# 2_ADSTM32-MCU.net
KiCad netlist of a schematic drawn in Altium Designer
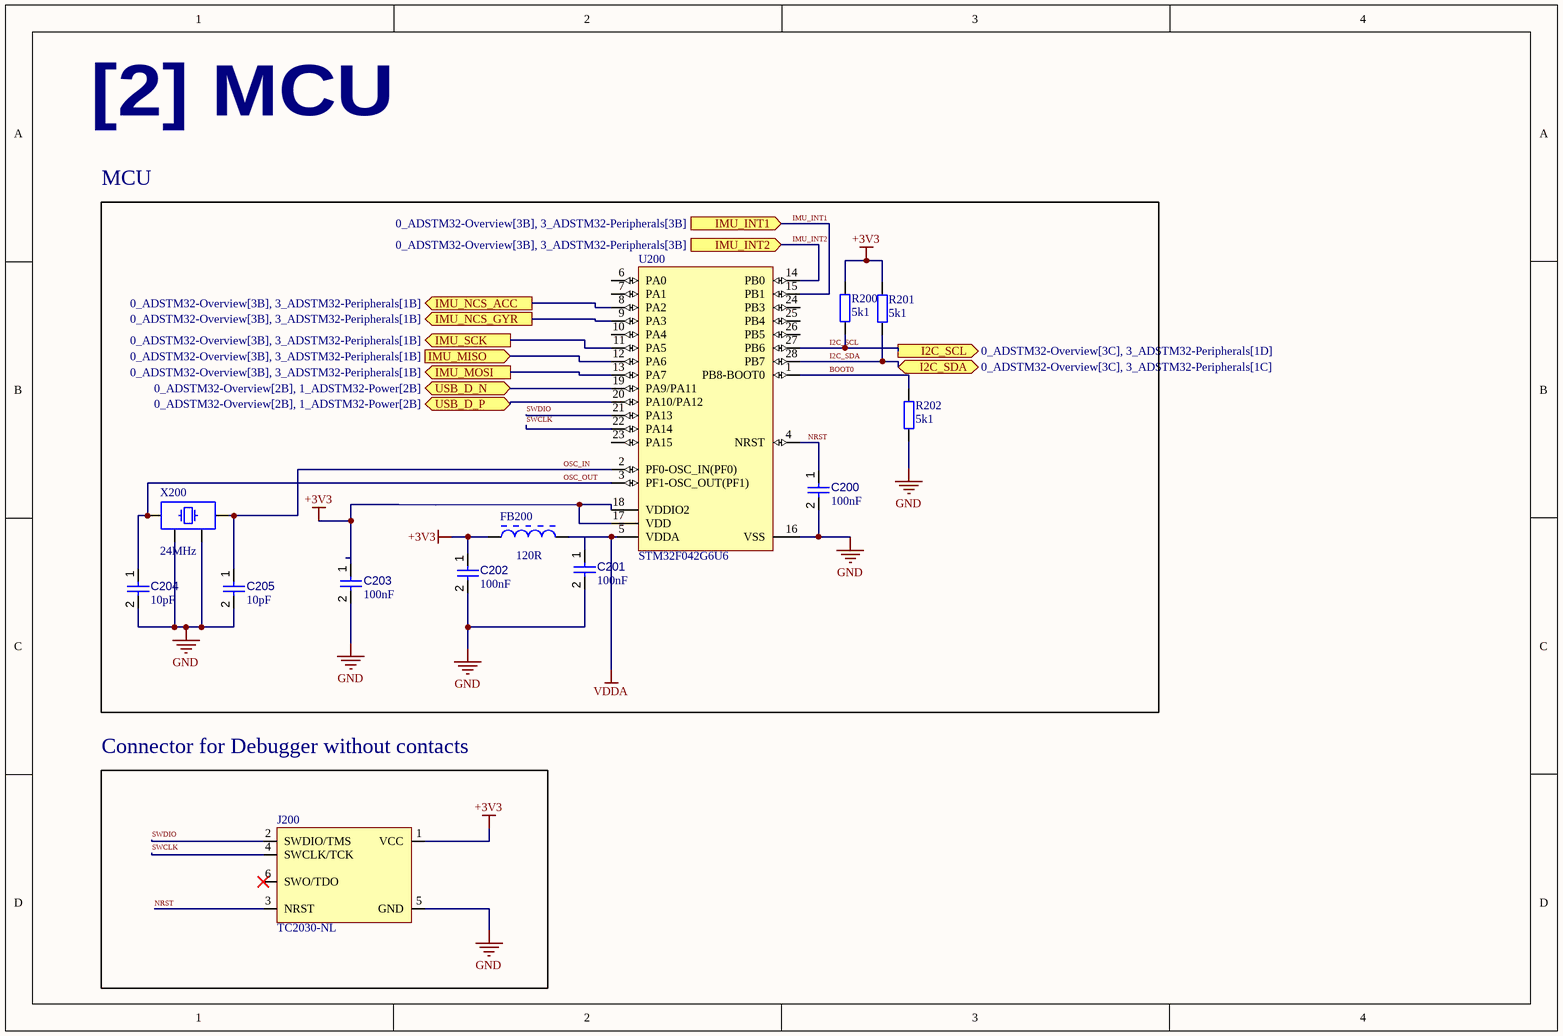
[diagram p0: 2_ADSTM32-MCU.SchDoc]

(export (version "E")
  (design (tool "Eeschema 10.0.6"))
  (components
    (comp (ref "C200")
      (value "100nF")
      (footprint "CAPC1608X90X40NL10T20")
      (description "Chip Capacitor, 100 nF, +/- 10%, 50 V, 0603 (1608 Metric)")
      (fields (field (name "TOLERANCE") "10%") (field (name "Comment") "Capacitor 100 nF +/-10% 50 V 0603"))
      (libsource (lib "Technische Universität Darmstadt -  Institut für Stromrichtertechnik und Antriebsregelung") (part "CAP-NP-2"))
    )
    (comp (ref "C201")
      (value "100nF")
      (footprint "CAPC1608X90X40NL10T20")
      (description "Chip Capacitor, 100 nF, +/- 10%, 50 V, 0603 (1608 Metric)")
      (fields (field (name "TOLERANCE") "10%") (field (name "Comment") "Capacitor 100 nF +/-10% 50 V 0603"))
      (libsource (lib "Technische Universität Darmstadt -  Institut für Stromrichtertechnik und Antriebsregelung") (part "CAP-NP-2"))
    )
    (comp (ref "C202")
      (value "100nF")
      (footprint "CAPC1608X90X40NL10T20")
      (description "Chip Capacitor, 100 nF, +/- 10%, 50 V, 0603 (1608 Metric)")
      (fields (field (name "TOLERANCE") "10%") (field (name "Comment") "Capacitor 100 nF +/-10% 50 V 0603"))
      (libsource (lib "Technische Universität Darmstadt -  Institut für Stromrichtertechnik und Antriebsregelung") (part "CAP-NP-2"))
    )
    (comp (ref "C203")
      (value "100nF")
      (footprint "CAPC1608X90X40NL10T20")
      (description "Chip Capacitor, 100 nF, +/- 10%, 50 V, 0603 (1608 Metric)")
      (fields (field (name "TOLERANCE") "10%") (field (name "Comment") "Capacitor 100 nF +/-10% 50 V 0603"))
      (libsource (lib "Technische Universität Darmstadt -  Institut für Stromrichtertechnik und Antriebsregelung") (part "CAP-NP-2"))
    )
    (comp (ref "C204")
      (value "10pF")
      (footprint "CAPC1608X90X40NL10T20")
      (description "Chip Capacitor, 100 nF, +/- 10%, 50 V, 0603 (1608 Metric)")
      (fields (field (name "TOLERANCE") "10%") (field (name "Comment") "Capacitor 100 nF +/-10% 50 V 0603"))
      (libsource (lib "Technische Universität Darmstadt -  Institut für Stromrichtertechnik und Antriebsregelung") (part "CAP-NP-2"))
    )
    (comp (ref "C205")
      (value "10pF")
      (footprint "CAPC1608X90X40NL10T20")
      (description "Chip Capacitor, 100 nF, +/- 10%, 50 V, 0603 (1608 Metric)")
      (fields (field (name "TOLERANCE") "10%") (field (name "Comment") "Capacitor 100 nF +/-10% 50 V 0603"))
      (libsource (lib "Technische Universität Darmstadt -  Institut für Stromrichtertechnik und Antriebsregelung") (part "CAP-NP-2"))
    )
    (comp (ref "FB200")
      (value "120R")
      (footprint "INDC2013X105X50ML20T20")
      (description "Chip Ferrite Bead, 120 Ohm,")
      (fields (field (name "TOLERANCE") "25%") (field (name "MANUFACTURER") "Murata"))
      (libsource (lib "Technische Universität Darmstadt -  Institut für Stromrichtertechnik und Antriebsregelung") (part "IND-FB-2"))
    )
    (comp (ref "J200")
      (value "TC2030-NL")
      (footprint "TC2030-NL-FP")
      (description "Tag-Connect No-Solder SWD Debug Connector (No Legs) DO NOT PLACE")
      (fields
        (field (name "MANUFACTURER") "Tag-Connect")
        (field (name "MANUFACTURER PART NUMBER") "TC2030-NL-FP")
      )
      (libsource (lib "Schematic-Lib-PhilsLab") (part "TC2030-NL"))
    )
    (comp (ref "R200")
      (value "5k1")
      (footprint "RES_0603")
      (description "Resistor SMD 0603")
      (libsource (lib "Schematic-Lib-PhilsLab") (part "RES_0603"))
    )
    (comp (ref "R201")
      (value "5k1")
      (footprint "RES_0603")
      (description "Resistor SMD 0603")
      (libsource (lib "Schematic-Lib-PhilsLab") (part "RES_0603"))
    )
    (comp (ref "R202")
      (value "5k1")
      (footprint "RES_0603")
      (description "Resistor SMD 0603")
      (libsource (lib "Schematic-Lib-PhilsLab") (part "RES_0603"))
    )
    (comp (ref "U200")
      (value "STM32F042G6U6")
      (footprint "STM-UFQFPN28_V")
      (fields (field (name "MANUFACTURER") "STMicroelectronics"))
      (libsource (lib "Altium Content Vault") (part "MC-ARM-STM32F042-UFQFPN28"))
    )
    (comp (ref "X200")
      (value "24MHz")
      (footprint "XTAL_3225")
      (description "Crystal SMD 24MHz 10PPM 7pF 3225")
      (fields
        (field (name "MANUFACTURER") "Epson")
        (field (name "MANUFACTURER PART NUMBER") "TSX-3225 24.0000MF15X-AC")
      )
      (libsource (lib "Schematic-Lib-PhilsLab") (part "TSX-3225_24.0000MF15X-AC"))
    )
  )
  (nets
    (net (code "1") (name "+3V3") (class "Default")
      (node (ref "C202") (pin "1") (pinfunction "1_1") (pintype "passive"))
      (node (ref "C203") (pin "1") (pinfunction "1_1") (pintype "passive"))
      (node (ref "FB200") (pin "1") (pinfunction "1_1") (pintype "passive"))
      (node (ref "J200") (pin "1") (pinfunction "VCC_1") (pintype "passive"))
      (node (ref "R200") (pin "2") (pinfunction "2_2") (pintype "passive"))
      (node (ref "R201") (pin "2") (pinfunction "2_2") (pintype "passive"))
      (node (ref "U200") (pin "17") (pinfunction "VDD_17") (pintype "power_in"))
      (node (ref "U200") (pin "18") (pinfunction "VDDIO2_18") (pintype "power_in"))
    )
    (net (code "2") (name "/BOOT0") (class "Default")
      (node (ref "R202") (pin "2") (pinfunction "2_2") (pintype "passive"))
      (node (ref "U200") (pin "1") (pinfunction "PB8-BOOT0_1") (pintype "bidirectional"))
    )
    (net (code "3") (name "/I2C_SCL") (class "Default")
      (node (ref "R200") (pin "1") (pinfunction "1_1") (pintype "passive"))
      (node (ref "U200") (pin "27") (pinfunction "PB6_27") (pintype "bidirectional"))
    )
    (net (code "4") (name "/I2C_SDA") (class "Default")
      (node (ref "R201") (pin "1") (pinfunction "1_1") (pintype "passive"))
      (node (ref "U200") (pin "28") (pinfunction "PB7_28") (pintype "bidirectional"))
    )
    (net (code "5") (name "/IMU_INT1") (class "Default")
      (node (ref "U200") (pin "15") (pinfunction "PB1_15") (pintype "bidirectional"))
    )
    (net (code "6") (name "/IMU_INT2") (class "Default")
      (node (ref "U200") (pin "14") (pinfunction "PB0_14") (pintype "bidirectional"))
    )
    (net (code "7") (name "/IMU_MISO") (class "Default")
      (node (ref "U200") (pin "12") (pinfunction "PA6_12") (pintype "bidirectional"))
    )
    (net (code "8") (name "/IMU_MOSI") (class "Default")
      (node (ref "U200") (pin "13") (pinfunction "PA7_13") (pintype "bidirectional"))
    )
    (net (code "9") (name "/IMU_NCS_ACC") (class "Default")
      (node (ref "U200") (pin "8") (pinfunction "PA2_8") (pintype "bidirectional"))
    )
    (net (code "10") (name "/IMU_NCS_GYR") (class "Default")
      (node (ref "U200") (pin "9") (pinfunction "PA3_9") (pintype "bidirectional"))
    )
    (net (code "11") (name "/IMU_SCK") (class "Default")
      (node (ref "U200") (pin "11") (pinfunction "PA5_11") (pintype "bidirectional"))
    )
    (net (code "12") (name "/NRST") (class "Default")
      (node (ref "C200") (pin "1") (pinfunction "1_1") (pintype "passive"))
      (node (ref "J200") (pin "3") (pinfunction "NRST_3") (pintype "passive"))
      (node (ref "U200") (pin "4") (pinfunction "NRST_4") (pintype "bidirectional"))
    )
    (net (code "13") (name "/OSC_IN") (class "Default")
      (node (ref "C205") (pin "1") (pinfunction "1_1") (pintype "passive"))
      (node (ref "U200") (pin "2") (pinfunction "PF0-OSC_IN(PF0)_2") (pintype "bidirectional"))
      (node (ref "X200") (pin "3") (pinfunction "3_3") (pintype "passive"))
    )
    (net (code "14") (name "/OSC_OUT") (class "Default")
      (node (ref "C204") (pin "1") (pinfunction "1_1") (pintype "passive"))
      (node (ref "U200") (pin "3") (pinfunction "PF1-OSC_OUT(PF1)_3") (pintype "bidirectional"))
      (node (ref "X200") (pin "1") (pinfunction "1_1") (pintype "passive"))
    )
    (net (code "15") (name "/SWCLK") (class "Default")
      (node (ref "J200") (pin "4") (pinfunction "SWCLK/TCK_4") (pintype "passive"))
      (node (ref "U200") (pin "22") (pinfunction "PA14_22") (pintype "bidirectional"))
    )
    (net (code "16") (name "/SWDIO") (class "Default")
      (node (ref "J200") (pin "2") (pinfunction "SWDIO/TMS_2") (pintype "passive"))
      (node (ref "U200") (pin "21") (pinfunction "PA13_21") (pintype "bidirectional"))
    )
    (net (code "17") (name "/USB_D_N") (class "Default")
      (node (ref "U200") (pin "19") (pinfunction "PA9/PA11_19") (pintype "bidirectional"))
    )
    (net (code "18") (name "/USB_D_P") (class "Default")
      (node (ref "U200") (pin "20") (pinfunction "PA10/PA12_20") (pintype "bidirectional"))
    )
    (net (code "19") (name "GND") (class "Default")
      (node (ref "C200") (pin "2") (pinfunction "2_2") (pintype "passive"))
      (node (ref "C201") (pin "2") (pinfunction "2_2") (pintype "passive"))
      (node (ref "C202") (pin "2") (pinfunction "2_2") (pintype "passive"))
      (node (ref "C203") (pin "2") (pinfunction "2_2") (pintype "passive"))
      (node (ref "C204") (pin "2") (pinfunction "2_2") (pintype "passive"))
      (node (ref "C205") (pin "2") (pinfunction "2_2") (pintype "passive"))
      (node (ref "J200") (pin "5") (pinfunction "GND_5") (pintype "passive"))
      (node (ref "R202") (pin "1") (pinfunction "1_1") (pintype "passive"))
      (node (ref "U200") (pin "16") (pinfunction "VSS_16") (pintype "power_in"))
      (node (ref "X200") (pin "2") (pinfunction "2_2") (pintype "passive"))
      (node (ref "X200") (pin "4") (pinfunction "4_4") (pintype "passive"))
    )
    (net (code "20") (name "VDDA") (class "Default")
      (node (ref "C201") (pin "1") (pinfunction "1_1") (pintype "passive"))
      (node (ref "FB200") (pin "2") (pinfunction "2_2") (pintype "passive"))
      (node (ref "U200") (pin "5") (pinfunction "VDDA_5") (pintype "power_in"))
    )
    (net (code "21") (name "unconnected-(J200-SWO{slash}TDO-Pad6)") (class "Default")
      (node (ref "J200") (pin "6") (pinfunction "SWO/TDO_6") (pintype "passive+no_connect"))
    )
    (net (code "22") (name "unconnected-(U200-PA0-Pad6)") (class "Default")
      (node (ref "U200") (pin "6") (pinfunction "PA0_6") (pintype "bidirectional"))
    )
    (net (code "23") (name "unconnected-(U200-PA1-Pad7)") (class "Default")
      (node (ref "U200") (pin "7") (pinfunction "PA1_7") (pintype "bidirectional"))
    )
    (net (code "24") (name "unconnected-(U200-PA4-Pad10)") (class "Default")
      (node (ref "U200") (pin "10") (pinfunction "PA4_10") (pintype "bidirectional"))
    )
    (net (code "25") (name "unconnected-(U200-PA15-Pad23)") (class "Default")
      (node (ref "U200") (pin "23") (pinfunction "PA15_23") (pintype "bidirectional"))
    )
    (net (code "26") (name "unconnected-(U200-PB3-Pad24)") (class "Default")
      (node (ref "U200") (pin "24") (pinfunction "PB3_24") (pintype "bidirectional"))
    )
    (net (code "27") (name "unconnected-(U200-PB4-Pad25)") (class "Default")
      (node (ref "U200") (pin "25") (pinfunction "PB4_25") (pintype "bidirectional"))
    )
    (net (code "28") (name "unconnected-(U200-PB5-Pad26)") (class "Default")
      (node (ref "U200") (pin "26") (pinfunction "PB5_26") (pintype "bidirectional"))
    )
  )
)
